# ICSP_Burn_Buffer.net
KiCad netlist of a schematic drawn in Altium Designer
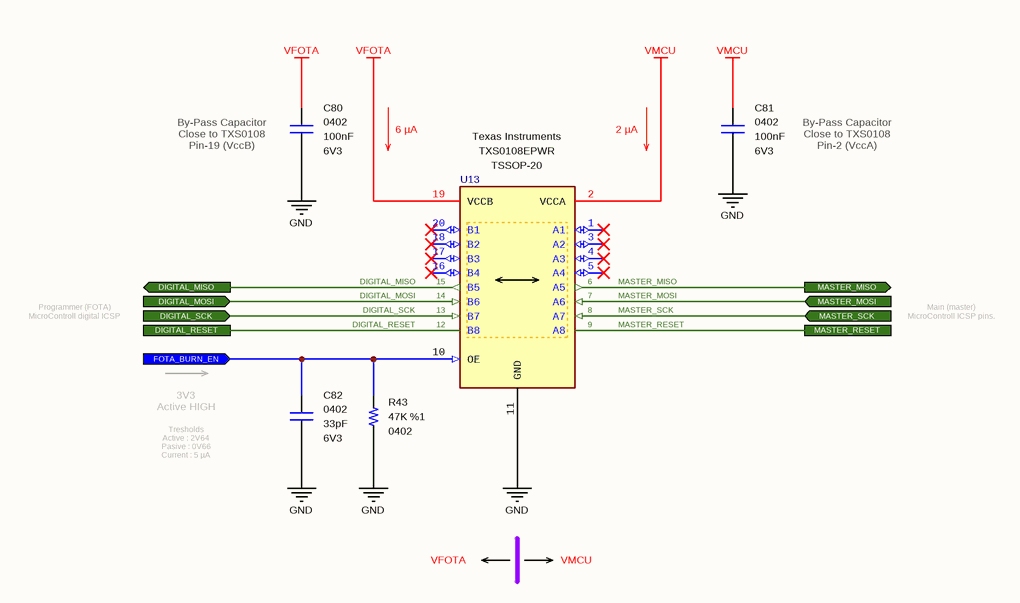
[diagram p0: ICSP Burn Buffer.SchDoc]

(export (version "E")
  (design (tool "Eeschema 10.0.6"))
  (components
    (comp (ref "C80")
      (value "100nF")
      (footprint "CAPACITOR_0402")
      (description "Capacitor - 100nF [0402-6V3] (Ceramic)")
      (fields
        (field (name "TOLERANCE") "%10")
        (field (name "CASE") "0402")
        (field (name "VOLTAGE") "6V3")
        (field (name "MANUFACTURER PART NUMBER") "04026D104KAT4A")
      )
      (libsource (lib "Ovoo_Library") (part "Capacitor - 100nF [0402-6V3]"))
    )
    (comp (ref "C81")
      (value "100nF")
      (footprint "CAPACITOR_0402")
      (description "Capacitor - 100nF [0402-6V3] (Ceramic)")
      (fields
        (field (name "TOLERANCE") "%10")
        (field (name "CASE") "0402")
        (field (name "VOLTAGE") "6V3")
        (field (name "MANUFACTURER PART NUMBER") "04026D104KAT4A")
      )
      (libsource (lib "Ovoo_Library") (part "Capacitor - 100nF [0402-6V3]"))
    )
    (comp (ref "C82")
      (value "33pF")
      (footprint "CAPACITOR_0402")
      (description "Capacitor - 33pF [0402] (Ceramic)")
      (fields
        (field (name "CASE") "0402")
        (field (name "TOLERANCE") "10%")
        (field (name "VOLTAGE") "6V3")
        (field (name "MANUFACTURER PART NUMBER") "C0402C330J9RACAUTO")
      )
      (libsource (lib "Ovoo_Library") (part "Capacitor - 33pF [0402-6V3]"))
    )
    (comp (ref "R43")
      (value "47K")
      (footprint "RESISTOR_0402")
      (description "Thick Film Resistors - SMD 1/16 W 47 Kohms 1%")
      (fields
        (field (name "TOLERANCE") "%1")
        (field (name "CASE") "0402")
        (field (name "MANUFACTURER PART NUMBER") "CRCW040247K0FKED")
        (field (name "Comment") "47K - 0402 - %1 - 1/16W")
      )
      (libsource (lib "Ovoo_Library") (part "Resistor - 47K"))
    )
    (comp (ref "U13")
      (value "Voltage Level Shifter")
      (footprint "TSSOP-20")
      (description "Translation - Voltage Levels 8B Bidir Vltg-Level Translator")
      (fields
        (field (name "MOUSER PART NUMBER") "595-TXS0108EPWR")
        (field (name "MANUFACTURER PART NUMBER") "TXS0108EPWR")
        (field (name "CASE") "TSSOP-20")
        (field (name "MANUFACTURER NAME") "Texas Instruments")
      )
      (libsource (lib "Ovoo_Library") (part "IC - TXS0108EPW"))
    )
  )
  (nets
    (net (code "1") (name "/DIGITAL_MISO") (class "Default")
      (node (ref "U13") (pin "15") (pinfunction "B5_15") (pintype "output"))
    )
    (net (code "2") (name "/DIGITAL_MOSI") (class "Default")
      (node (ref "U13") (pin "14") (pinfunction "B6_14") (pintype "input"))
    )
    (net (code "3") (name "/DIGITAL_RESET") (class "Default")
      (node (ref "U13") (pin "12") (pinfunction "B8_12") (pintype "passive"))
    )
    (net (code "4") (name "/DIGITAL_SCK") (class "Default")
      (node (ref "U13") (pin "13") (pinfunction "B7_13") (pintype "input"))
    )
    (net (code "5") (name "/FOTA_BURN_EN") (class "Default")
      (node (ref "C82") (pin "1") (pinfunction "1_1") (pintype "passive"))
      (node (ref "R43") (pin "2") (pinfunction "2_2") (pintype "passive"))
      (node (ref "U13") (pin "10") (pinfunction "OE_10") (pintype "input"))
    )
    (net (code "6") (name "/MASTER_MISO") (class "Default")
      (node (ref "U13") (pin "6") (pinfunction "A5_6") (pintype "output"))
    )
    (net (code "7") (name "/MASTER_MOSI") (class "Default")
      (node (ref "U13") (pin "7") (pinfunction "A6_7") (pintype "input"))
    )
    (net (code "8") (name "/MASTER_RESET") (class "Default")
      (node (ref "U13") (pin "9") (pinfunction "A8_9") (pintype "passive"))
    )
    (net (code "9") (name "/MASTER_SCK") (class "Default")
      (node (ref "U13") (pin "8") (pinfunction "A7_8") (pintype "input"))
    )
    (net (code "10") (name "GND") (class "Default")
      (node (ref "C80") (pin "1") (pinfunction "1_1") (pintype "passive"))
      (node (ref "C81") (pin "1") (pinfunction "1_1") (pintype "passive"))
      (node (ref "C82") (pin "2") (pinfunction "2_2") (pintype "passive"))
      (node (ref "R43") (pin "1") (pinfunction "1_1") (pintype "passive"))
      (node (ref "U13") (pin "11") (pinfunction "GND_11") (pintype "passive"))
    )
    (net (code "11") (name "VFOTA") (class "Default")
      (node (ref "C80") (pin "2") (pinfunction "2_2") (pintype "passive"))
      (node (ref "U13") (pin "19") (pinfunction "VCCB_19") (pintype "power_in"))
    )
    (net (code "12") (name "VMCU") (class "Default")
      (node (ref "C81") (pin "2") (pinfunction "2_2") (pintype "passive"))
      (node (ref "U13") (pin "2") (pinfunction "VCCA_2") (pintype "power_in"))
    )
    (net (code "13") (name "unconnected-(U13-A1-Pad1)") (class "Default")
      (node (ref "U13") (pin "1") (pinfunction "A1_1") (pintype "bidirectional+no_connect"))
    )
    (net (code "14") (name "unconnected-(U13-A2-Pad3)") (class "Default")
      (node (ref "U13") (pin "3") (pinfunction "A2_3") (pintype "bidirectional+no_connect"))
    )
    (net (code "15") (name "unconnected-(U13-A3-Pad4)") (class "Default")
      (node (ref "U13") (pin "4") (pinfunction "A3_4") (pintype "bidirectional+no_connect"))
    )
    (net (code "16") (name "unconnected-(U13-A4-Pad5)") (class "Default")
      (node (ref "U13") (pin "5") (pinfunction "A4_5") (pintype "bidirectional+no_connect"))
    )
    (net (code "17") (name "unconnected-(U13-B1-Pad20)") (class "Default")
      (node (ref "U13") (pin "20") (pinfunction "B1_20") (pintype "bidirectional+no_connect"))
    )
    (net (code "18") (name "unconnected-(U13-B2-Pad18)") (class "Default")
      (node (ref "U13") (pin "18") (pinfunction "B2_18") (pintype "bidirectional+no_connect"))
    )
    (net (code "19") (name "unconnected-(U13-B3-Pad17)") (class "Default")
      (node (ref "U13") (pin "17") (pinfunction "B3_17") (pintype "bidirectional+no_connect"))
    )
    (net (code "20") (name "unconnected-(U13-B4-Pad16)") (class "Default")
      (node (ref "U13") (pin "16") (pinfunction "B4_16") (pintype "bidirectional+no_connect"))
    )
  )
)
